# Mach_cau_H.net
KiCad netlist of a schematic drawn in Altium Designer
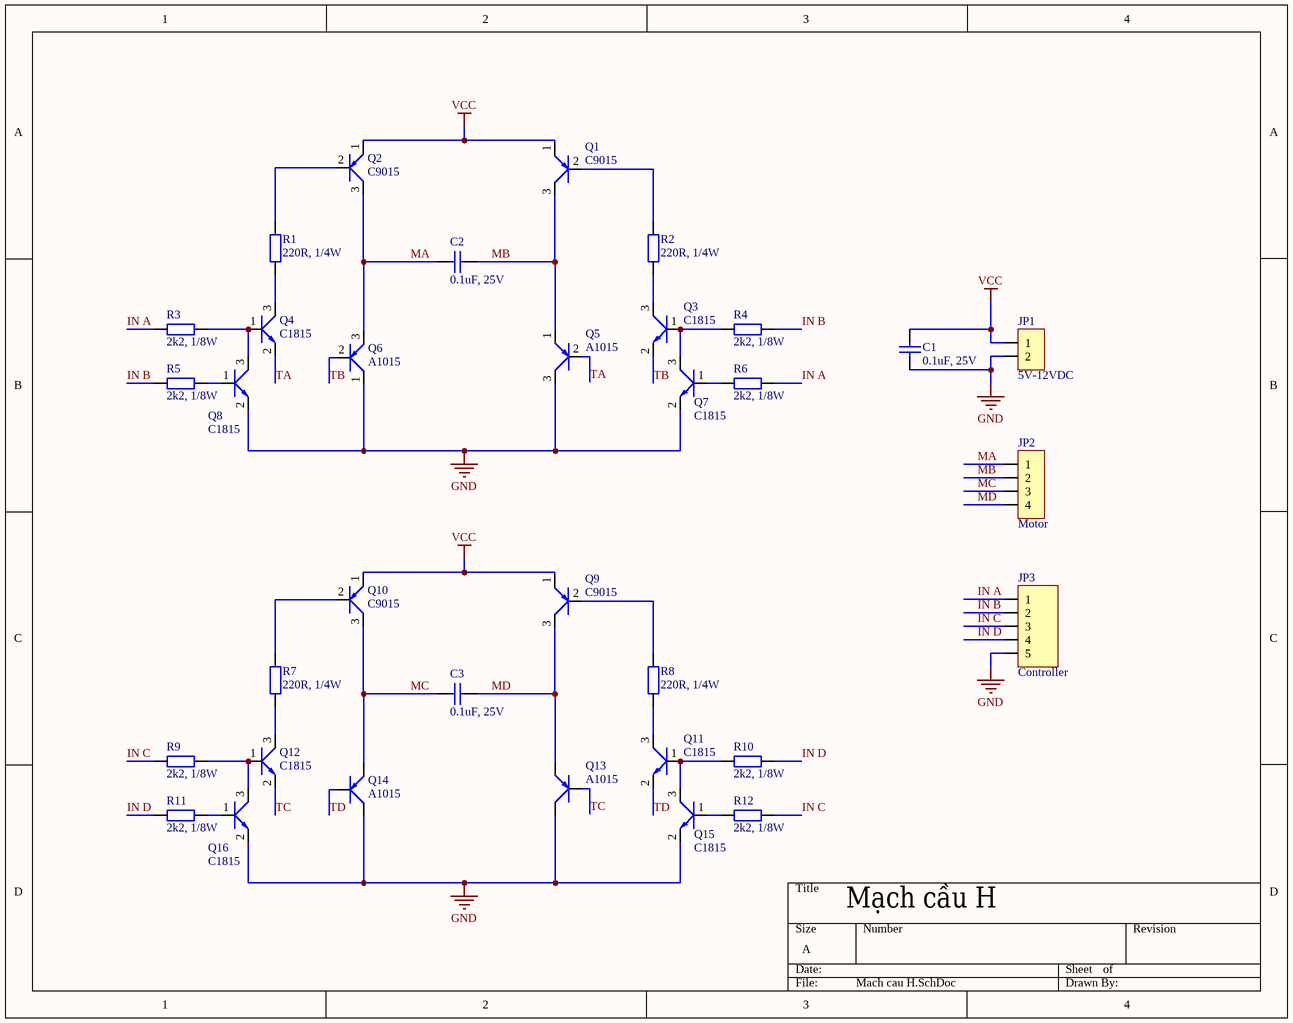
[diagram p0: Mach cau H.SchDoc]

(export (version "E")
  (design (tool "Eeschema 10.0.6"))
  (components
    (comp (ref "C1")
      (value "0.1uF, 25V")
      (footprint "tu gom")
      (description "Cắm")
      (libsource (lib "Tu dien") (part "Tu gom 101 50V"))
    )
    (comp (ref "C2")
      (value "0.1uF, 25V")
      (footprint "tu gom")
      (description "Cắm")
      (libsource (lib "Tu dien") (part "Tu gom 101 50V"))
    )
    (comp (ref "C3")
      (value "0.1uF, 25V")
      (footprint "tu gom")
      (description "Cắm")
      (libsource (lib "Tu dien") (part "Tu gom 101 50V"))
    )
    (comp (ref "JP1")
      (value "5V-12VDC")
      (footprint "JP 1x2 CT")
      (description "Cắm")
      (libsource (lib "Jump") (part "JP 1x2 2.54 Cai Thang"))
    )
    (comp (ref "JP2")
      (value "Motor")
      (footprint "JP 1x4 CT")
      (description "Cắm")
      (libsource (lib "Jump") (part "JP 1x4 2.54 Cai Thang"))
    )
    (comp (ref "JP3")
      (value "Controller")
      (footprint "JP 1x5 CT")
      (description "Cắm")
      (libsource (lib "Jump") (part "JP 1x5 2.54 Cai Thang"))
    )
    (comp (ref "Q1")
      (value "C9015")
      (footprint "QTO-92")
      (description "P 600mW, EBC")
      (libsource (lib "syhaunguyen") (part "PNP_EBC"))
    )
    (comp (ref "Q2")
      (value "C9015")
      (footprint "QTO-92")
      (description "P 600mW, EBC")
      (libsource (lib "syhaunguyen") (part "PNP_EBC"))
    )
    (comp (ref "Q3")
      (value "C1815")
      (footprint "QTO-92")
      (description "NPN 600mW, ECB")
      (libsource (lib "syhaunguyen") (part "C1815"))
    )
    (comp (ref "Q4")
      (value "C1815")
      (footprint "QTO-92")
      (description "NPN 600mW, ECB")
      (libsource (lib "syhaunguyen") (part "C1815"))
    )
    (comp (ref "Q5")
      (value "A1015")
      (footprint "TO92")
      (description "PNP 600mW, ECB")
      (libsource (lib "") (part "A1015_1"))
    )
    (comp (ref "Q6")
      (value "A1015")
      (footprint "TO92")
      (description "PNP 600mW, ECB")
      (libsource (lib "") (part "A1015_2"))
    )
    (comp (ref "Q7")
      (value "C1815")
      (footprint "QTO-92")
      (description "NPN 600mW, ECB")
      (libsource (lib "syhaunguyen") (part "C1815"))
    )
    (comp (ref "Q8")
      (value "C1815")
      (footprint "QTO-92")
      (description "NPN 600mW, ECB")
      (libsource (lib "syhaunguyen") (part "C1815"))
    )
    (comp (ref "Q9")
      (value "C9015")
      (footprint "QTO-92")
      (description "P 600mW, EBC")
      (libsource (lib "syhaunguyen") (part "PNP_EBC"))
    )
    (comp (ref "Q10")
      (value "C9015")
      (footprint "QTO-92")
      (description "P 600mW, EBC")
      (libsource (lib "syhaunguyen") (part "PNP_EBC"))
    )
    (comp (ref "Q11")
      (value "C1815")
      (footprint "QTO-92")
      (description "NPN 600mW, ECB")
      (libsource (lib "syhaunguyen") (part "C1815"))
    )
    (comp (ref "Q12")
      (value "C1815")
      (footprint "QTO-92")
      (description "NPN 600mW, ECB")
      (libsource (lib "syhaunguyen") (part "C1815"))
    )
    (comp (ref "Q13")
      (value "A1015")
      (footprint "TO92")
      (description "PNP 600mW, ECB")
      (libsource (lib "TranFet") (part "A1015"))
    )
    (comp (ref "Q14")
      (value "A1015")
      (footprint "TO92")
      (description "PNP 600mW, ECB")
      (libsource (lib "TranFet") (part "A1015"))
    )
    (comp (ref "Q15")
      (value "C1815")
      (footprint "QTO-92")
      (description "NPN 600mW, ECB")
      (libsource (lib "syhaunguyen") (part "C1815"))
    )
    (comp (ref "Q16")
      (value "C1815")
      (footprint "QTO-92")
      (description "NPN 600mW, ECB")
      (libsource (lib "syhaunguyen") (part "C1815"))
    )
    (comp (ref "R1")
      (value "220R, 1/4W")
      (footprint "tro vach 1/4w")
      (description "Cắm")
      (libsource (lib "Dien Tro") (part "Tro Vach 1/4W 5% 220R"))
    )
    (comp (ref "R2")
      (value "220R, 1/4W")
      (footprint "tro vach 1/4w")
      (description "Cắm")
      (libsource (lib "Dien Tro") (part "Tro Vach 1/4W 5% 220R"))
    )
    (comp (ref "R3")
      (value "2k2, 1/8W")
      (footprint "R1/4W")
      (description "Resistor 1/4W")
      (libsource (lib "syhaunguyen") (part "R1/4W"))
    )
    (comp (ref "R4")
      (value "2k2, 1/8W")
      (footprint "R1/4W")
      (description "Resistor 1/4W")
      (libsource (lib "syhaunguyen") (part "R1/4W"))
    )
    (comp (ref "R5")
      (value "2k2, 1/8W")
      (footprint "R1/4W")
      (description "Resistor 1/4W")
      (libsource (lib "syhaunguyen") (part "R1/4W"))
    )
    (comp (ref "R6")
      (value "2k2, 1/8W")
      (footprint "R1/4W")
      (description "Resistor 1/4W")
      (libsource (lib "syhaunguyen") (part "R1/4W"))
    )
    (comp (ref "R7")
      (value "220R, 1/4W")
      (footprint "tro vach 1/4w")
      (description "Cắm")
      (libsource (lib "Dien Tro") (part "Tro Vach 1/4W 5% 220R"))
    )
    (comp (ref "R8")
      (value "220R, 1/4W")
      (footprint "tro vach 1/4w")
      (description "Cắm")
      (libsource (lib "Dien Tro") (part "Tro Vach 1/4W 5% 220R"))
    )
    (comp (ref "R9")
      (value "2k2, 1/8W")
      (footprint "R1/4W")
      (description "Resistor 1/4W")
      (libsource (lib "syhaunguyen") (part "R1/4W"))
    )
    (comp (ref "R10")
      (value "2k2, 1/8W")
      (footprint "R1/4W")
      (description "Resistor 1/4W")
      (libsource (lib "syhaunguyen") (part "R1/4W"))
    )
    (comp (ref "R11")
      (value "2k2, 1/8W")
      (footprint "R1/4W")
      (description "Resistor 1/4W")
      (libsource (lib "syhaunguyen") (part "R1/4W"))
    )
    (comp (ref "R12")
      (value "2k2, 1/8W")
      (footprint "R1/4W")
      (description "Resistor 1/4W")
      (libsource (lib "syhaunguyen") (part "R1/4W"))
    )
  )
  (nets
    (net (code "1") (name "/IN A") (class "Default")
      (node (ref "JP3") (pin "1") (pinfunction "1_1") (pintype "passive"))
      (node (ref "R3") (pin "1") (pinfunction "1_1") (pintype "passive"))
      (node (ref "R6") (pin "1") (pinfunction "1_1") (pintype "passive"))
    )
    (net (code "2") (name "/IN B") (class "Default")
      (node (ref "JP3") (pin "2") (pinfunction "2_2") (pintype "passive"))
      (node (ref "R4") (pin "1") (pinfunction "1_1") (pintype "passive"))
      (node (ref "R5") (pin "1") (pinfunction "1_1") (pintype "passive"))
    )
    (net (code "3") (name "/IN C") (class "Default")
      (node (ref "JP3") (pin "3") (pinfunction "3_3") (pintype "passive"))
      (node (ref "R12") (pin "1") (pinfunction "1_1") (pintype "passive"))
      (node (ref "R9") (pin "1") (pinfunction "1_1") (pintype "passive"))
    )
    (net (code "4") (name "/IN D") (class "Default")
      (node (ref "JP3") (pin "4") (pinfunction "4_4") (pintype "passive"))
      (node (ref "R10") (pin "1") (pinfunction "1_1") (pintype "passive"))
      (node (ref "R11") (pin "1") (pinfunction "1_1") (pintype "passive"))
    )
    (net (code "5") (name "/MA") (class "Default")
      (node (ref "C2") (pin "1") (pinfunction "1_1") (pintype "passive"))
      (node (ref "JP2") (pin "1") (pinfunction "1_1") (pintype "passive"))
      (node (ref "Q2") (pin "3") (pinfunction "C_3") (pintype "passive"))
      (node (ref "Q6") (pin "3") (pinfunction "C_3") (pintype "passive"))
    )
    (net (code "6") (name "/MB") (class "Default")
      (node (ref "C2") (pin "2") (pinfunction "2_2") (pintype "passive"))
      (node (ref "JP2") (pin "2") (pinfunction "2_2") (pintype "passive"))
      (node (ref "Q1") (pin "3") (pinfunction "C_3") (pintype "passive"))
      (node (ref "Q5") (pin "1") (pinfunction "C_1") (pintype "passive"))
    )
    (net (code "7") (name "/MC") (class "Default")
      (node (ref "C3") (pin "1") (pinfunction "1_1") (pintype "passive"))
      (node (ref "JP2") (pin "3") (pinfunction "3_3") (pintype "passive"))
      (node (ref "Q10") (pin "3") (pinfunction "C_3") (pintype "passive"))
      (node (ref "Q14") (pin "1") (pinfunction "E_1") (pintype "passive"))
    )
    (net (code "8") (name "/MD") (class "Default")
      (node (ref "C3") (pin "2") (pinfunction "2_2") (pintype "passive"))
      (node (ref "JP2") (pin "4") (pinfunction "4_4") (pintype "passive"))
      (node (ref "Q13") (pin "1") (pinfunction "E_1") (pintype "passive"))
      (node (ref "Q9") (pin "3") (pinfunction "C_3") (pintype "passive"))
    )
    (net (code "9") (name "/TA") (class "Default")
      (node (ref "Q4") (pin "2") (pinfunction "E_2") (pintype "passive"))
      (node (ref "Q5") (pin "2") (pinfunction "B_2") (pintype "passive"))
    )
    (net (code "10") (name "/TB") (class "Default")
      (node (ref "Q3") (pin "2") (pinfunction "E_2") (pintype "passive"))
      (node (ref "Q6") (pin "2") (pinfunction "B_2") (pintype "passive"))
    )
    (net (code "11") (name "/TC") (class "Default")
      (node (ref "Q12") (pin "2") (pinfunction "E_2") (pintype "passive"))
      (node (ref "Q13") (pin "3") (pinfunction "B_3") (pintype "passive"))
    )
    (net (code "12") (name "/TD") (class "Default")
      (node (ref "Q11") (pin "2") (pinfunction "E_2") (pintype "passive"))
      (node (ref "Q14") (pin "3") (pinfunction "B_3") (pintype "passive"))
    )
    (net (code "13") (name "GND") (class "Default")
      (node (ref "C1") (pin "2") (pinfunction "2_2") (pintype "passive"))
      (node (ref "JP1") (pin "2") (pinfunction "2_2") (pintype "passive"))
      (node (ref "JP3") (pin "5") (pinfunction "5_5") (pintype "passive"))
      (node (ref "Q13") (pin "2") (pinfunction "C_2") (pintype "passive"))
      (node (ref "Q14") (pin "2") (pinfunction "C_2") (pintype "passive"))
      (node (ref "Q15") (pin "2") (pinfunction "E_2") (pintype "passive"))
      (node (ref "Q16") (pin "2") (pinfunction "E_2") (pintype "passive"))
      (node (ref "Q5") (pin "3") (pinfunction "E_3") (pintype "passive"))
      (node (ref "Q6") (pin "1") (pinfunction "E_1") (pintype "passive"))
      (node (ref "Q7") (pin "2") (pinfunction "E_2") (pintype "passive"))
      (node (ref "Q8") (pin "2") (pinfunction "E_2") (pintype "passive"))
    )
    (net (code "14") (name "Net-(Q1-B)") (class "Default")
      (node (ref "Q1") (pin "2") (pinfunction "B_2") (pintype "passive"))
      (node (ref "R2") (pin "2") (pinfunction "2_2") (pintype "passive"))
    )
    (net (code "15") (name "Net-(Q2-B)") (class "Default")
      (node (ref "Q2") (pin "2") (pinfunction "B_2") (pintype "passive"))
      (node (ref "R1") (pin "2") (pinfunction "2_2") (pintype "passive"))
    )
    (net (code "16") (name "Net-(Q3-B)") (class "Default")
      (node (ref "Q3") (pin "1") (pinfunction "B_1") (pintype "passive"))
      (node (ref "Q7") (pin "3") (pinfunction "C_3") (pintype "passive"))
      (node (ref "R4") (pin "2") (pinfunction "2_2") (pintype "passive"))
    )
    (net (code "17") (name "Net-(Q3-C)") (class "Default")
      (node (ref "Q3") (pin "3") (pinfunction "C_3") (pintype "passive"))
      (node (ref "R2") (pin "1") (pinfunction "1_1") (pintype "passive"))
    )
    (net (code "18") (name "Net-(Q4-B)") (class "Default")
      (node (ref "Q4") (pin "1") (pinfunction "B_1") (pintype "passive"))
      (node (ref "Q8") (pin "3") (pinfunction "C_3") (pintype "passive"))
      (node (ref "R3") (pin "2") (pinfunction "2_2") (pintype "passive"))
    )
    (net (code "19") (name "Net-(Q4-C)") (class "Default")
      (node (ref "Q4") (pin "3") (pinfunction "C_3") (pintype "passive"))
      (node (ref "R1") (pin "1") (pinfunction "1_1") (pintype "passive"))
    )
    (net (code "20") (name "Net-(Q7-B)") (class "Default")
      (node (ref "Q7") (pin "1") (pinfunction "B_1") (pintype "passive"))
      (node (ref "R6") (pin "2") (pinfunction "2_2") (pintype "passive"))
    )
    (net (code "21") (name "Net-(Q8-B)") (class "Default")
      (node (ref "Q8") (pin "1") (pinfunction "B_1") (pintype "passive"))
      (node (ref "R5") (pin "2") (pinfunction "2_2") (pintype "passive"))
    )
    (net (code "22") (name "Net-(Q9-B)") (class "Default")
      (node (ref "Q9") (pin "2") (pinfunction "B_2") (pintype "passive"))
      (node (ref "R8") (pin "2") (pinfunction "2_2") (pintype "passive"))
    )
    (net (code "23") (name "Net-(Q10-B)") (class "Default")
      (node (ref "Q10") (pin "2") (pinfunction "B_2") (pintype "passive"))
      (node (ref "R7") (pin "2") (pinfunction "2_2") (pintype "passive"))
    )
    (net (code "24") (name "Net-(Q11-B)") (class "Default")
      (node (ref "Q11") (pin "1") (pinfunction "B_1") (pintype "passive"))
      (node (ref "Q15") (pin "3") (pinfunction "C_3") (pintype "passive"))
      (node (ref "R10") (pin "2") (pinfunction "2_2") (pintype "passive"))
    )
    (net (code "25") (name "Net-(Q11-C)") (class "Default")
      (node (ref "Q11") (pin "3") (pinfunction "C_3") (pintype "passive"))
      (node (ref "R8") (pin "1") (pinfunction "1_1") (pintype "passive"))
    )
    (net (code "26") (name "Net-(Q12-B)") (class "Default")
      (node (ref "Q12") (pin "1") (pinfunction "B_1") (pintype "passive"))
      (node (ref "Q16") (pin "3") (pinfunction "C_3") (pintype "passive"))
      (node (ref "R9") (pin "2") (pinfunction "2_2") (pintype "passive"))
    )
    (net (code "27") (name "Net-(Q12-C)") (class "Default")
      (node (ref "Q12") (pin "3") (pinfunction "C_3") (pintype "passive"))
      (node (ref "R7") (pin "1") (pinfunction "1_1") (pintype "passive"))
    )
    (net (code "28") (name "Net-(Q15-B)") (class "Default")
      (node (ref "Q15") (pin "1") (pinfunction "B_1") (pintype "passive"))
      (node (ref "R12") (pin "2") (pinfunction "2_2") (pintype "passive"))
    )
    (net (code "29") (name "Net-(Q16-B)") (class "Default")
      (node (ref "Q16") (pin "1") (pinfunction "B_1") (pintype "passive"))
      (node (ref "R11") (pin "2") (pinfunction "2_2") (pintype "passive"))
    )
    (net (code "30") (name "VCC") (class "Default")
      (node (ref "C1") (pin "1") (pinfunction "1_1") (pintype "passive"))
      (node (ref "JP1") (pin "1") (pinfunction "1_1") (pintype "passive"))
      (node (ref "Q1") (pin "1") (pinfunction "E_1") (pintype "passive"))
      (node (ref "Q10") (pin "1") (pinfunction "E_1") (pintype "passive"))
      (node (ref "Q2") (pin "1") (pinfunction "E_1") (pintype "passive"))
      (node (ref "Q9") (pin "1") (pinfunction "E_1") (pintype "passive"))
    )
  )
)
